# working.net
KiCad netlist of a schematic drawn in EAGLE
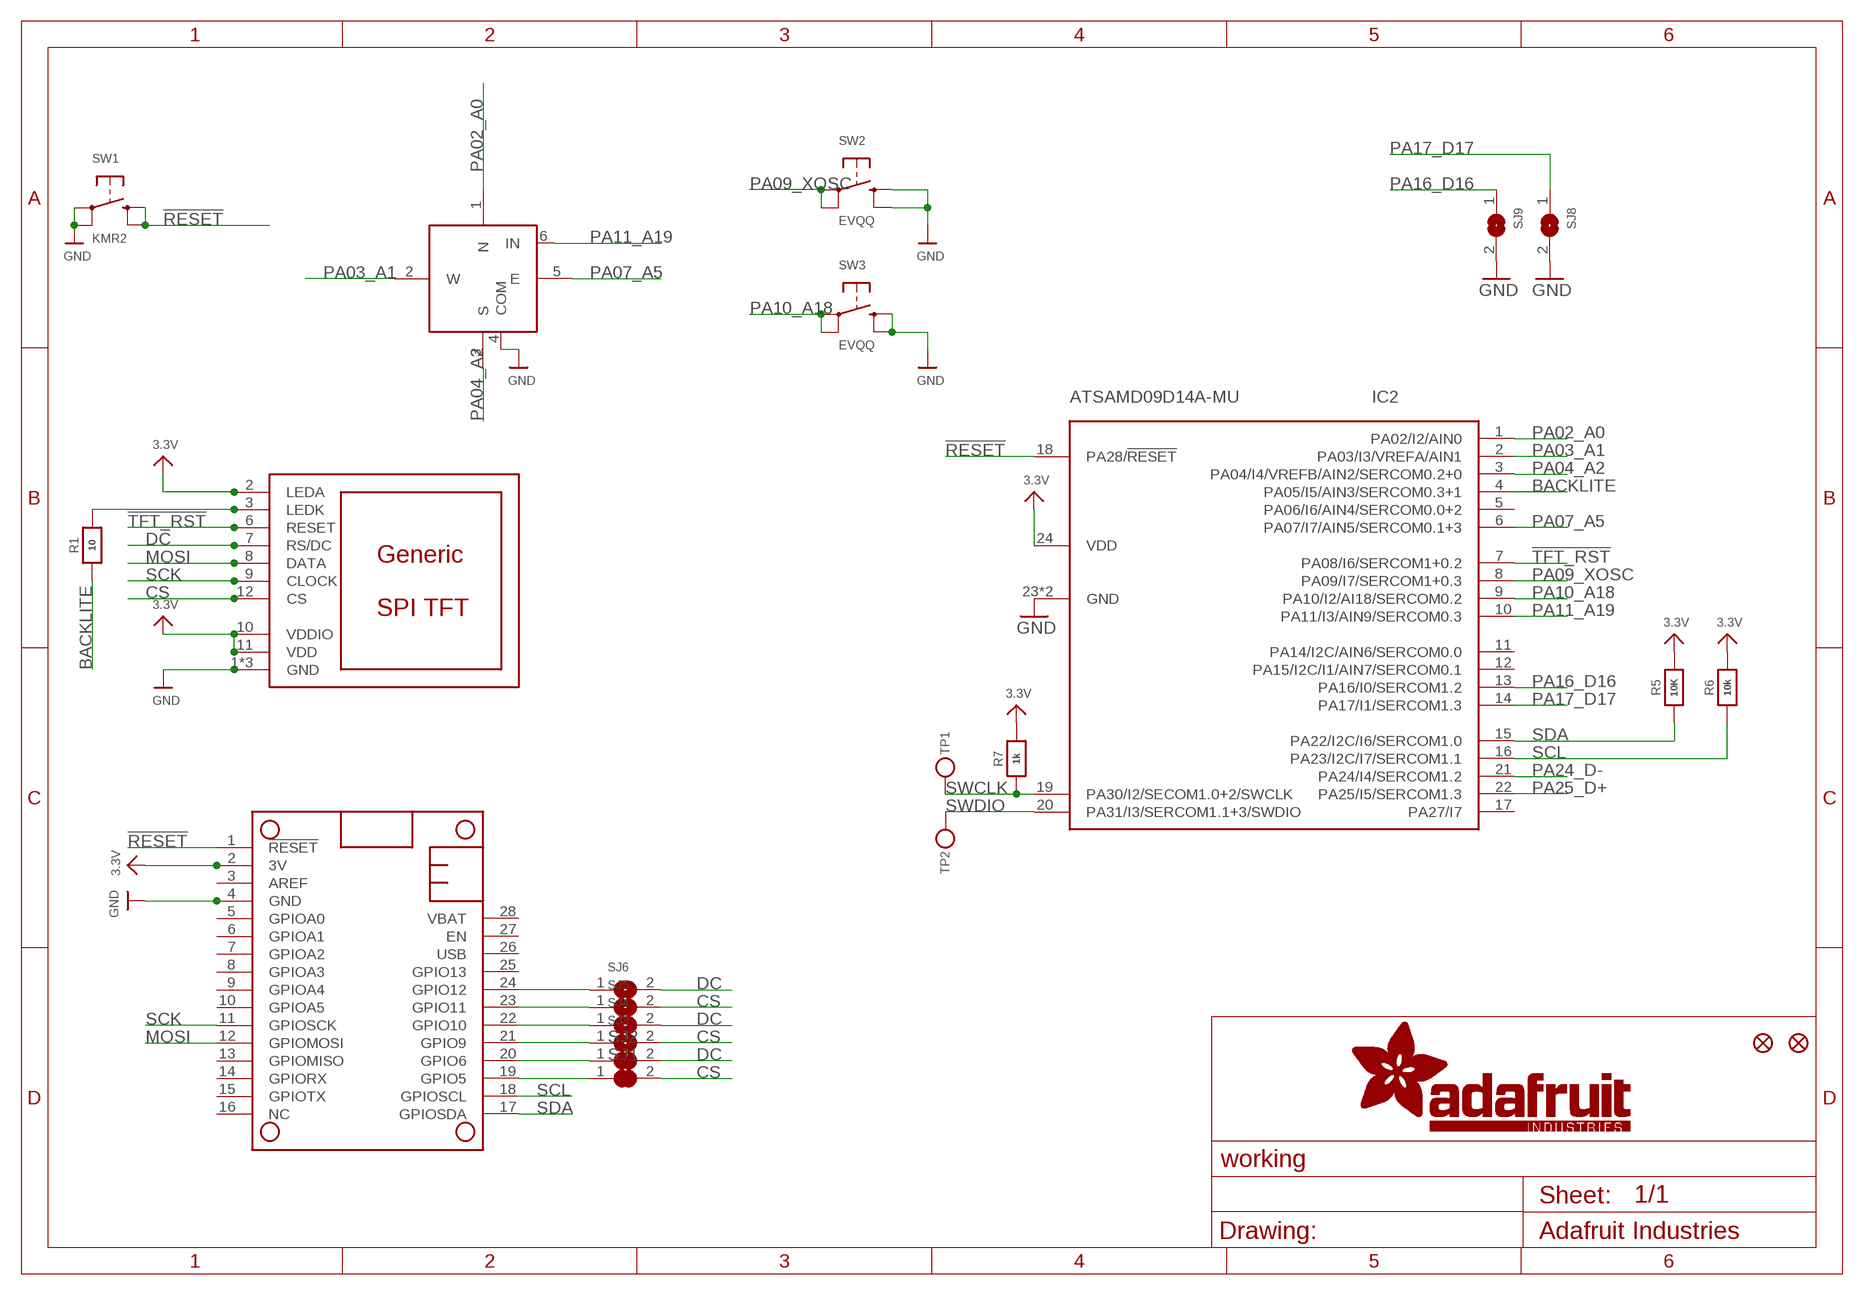
[diagram p0: schematic, sheet 1]

(export (version "E")
  (design (tool "Eeschema 10.0.6"))
  (components
    (comp (ref "FID1")
      (value "FIDUCIAL_1MM")
      (footprint "eagle-import:FIDUCIAL_1MM")
      (libsource (lib "eagle-import") (part "FIDUCIAL_1MM"))
    )
    (comp (ref "FID2")
      (value "FIDUCIAL_1MM")
      (footprint "eagle-import:FIDUCIAL_1MM")
      (libsource (lib "eagle-import") (part "FIDUCIAL_1MM"))
    )
    (comp (ref "IC2")
      (value "ATSAMD09D14A-MU")
      (footprint "eagle-import:QFN24_4MM")
      (libsource (lib "eagle-import") (part "ATSAMD09D14A-MU"))
    )
    (comp (ref "MS1")
      (value "FEATHERWING")
      (footprint "eagle-import:FEATHERWING")
      (libsource (lib "eagle-import") (part "FEATHERWING"))
    )
    (comp (ref "R1")
      (value "10")
      (footprint "eagle-import:0603-NO")
      (libsource (lib "eagle-import") (part "RESISTOR_0603_NOOUT"))
    )
    (comp (ref "R5")
      (value "10K")
      (footprint "eagle-import:0603-NO")
      (libsource (lib "eagle-import") (part "RESISTOR_0603_NOOUT"))
    )
    (comp (ref "R6")
      (value "10k")
      (footprint "eagle-import:0603-NO")
      (libsource (lib "eagle-import") (part "RESISTOR_0603_NOOUT"))
    )
    (comp (ref "R7")
      (value "1k")
      (footprint "eagle-import:0603-NO")
      (libsource (lib "eagle-import") (part "RESISTOR_0603_NOOUT"))
    )
    (comp (ref "SJ1")
      (value "SOLDERJUMPER_CLOSED")
      (footprint "eagle-import:SOLDERJUMPER_CLOSEDWIRE")
      (libsource (lib "eagle-import") (part "SOLDERJUMPER_CLOSED"))
    )
    (comp (ref "SJ2")
      (value "SOLDERJUMPER_CLOSED")
      (footprint "eagle-import:SOLDERJUMPER_CLOSEDWIRE")
      (libsource (lib "eagle-import") (part "SOLDERJUMPER_CLOSED"))
    )
    (comp (ref "SJ3")
      (value "SOLDERJUMPER")
      (footprint "eagle-import:SOLDERJUMPER_ARROW_NOPASTE")
      (libsource (lib "eagle-import") (part "SOLDERJUMPER"))
    )
    (comp (ref "SJ4")
      (value "SOLDERJUMPER")
      (footprint "eagle-import:SOLDERJUMPER_ARROW_NOPASTE")
      (libsource (lib "eagle-import") (part "SOLDERJUMPER"))
    )
    (comp (ref "SJ5")
      (value "SOLDERJUMPER")
      (footprint "eagle-import:SOLDERJUMPER_ARROW_NOPASTE")
      (libsource (lib "eagle-import") (part "SOLDERJUMPER"))
    )
    (comp (ref "SJ6")
      (value "SOLDERJUMPER")
      (footprint "eagle-import:SOLDERJUMPER_ARROW_NOPASTE")
      (libsource (lib "eagle-import") (part "SOLDERJUMPER"))
    )
    (comp (ref "SJ8")
      (value "SOLDERJUMPER")
      (footprint "eagle-import:SOLDERJUMPER_ARROW_NOPASTE")
      (libsource (lib "eagle-import") (part "SOLDERJUMPER"))
    )
    (comp (ref "SJ9")
      (value "SOLDERJUMPER")
      (footprint "eagle-import:SOLDERJUMPER_ARROW_NOPASTE")
      (libsource (lib "eagle-import") (part "SOLDERJUMPER"))
    )
    (comp (ref "SW1")
      (value "KMR2")
      (footprint "eagle-import:BTN_KMR2_4.6X2.8")
      (libsource (lib "eagle-import") (part "SWITCH_TACT_SMT4.6X2.8"))
    )
    (comp (ref "SW2")
      (value "EVQQ")
      (footprint "eagle-import:EVQ-Q2_SMALLER")
      (libsource (lib "eagle-import") (part "SWITCH_TACT_SMT_EVQQ2_SMALL"))
    )
    (comp (ref "SW3")
      (value "EVQQ")
      (footprint "eagle-import:EVQ-Q2_SMALLER")
      (libsource (lib "eagle-import") (part "SWITCH_TACT_SMT_EVQQ2_SMALL"))
    )
    (comp (ref "SW4")
      (value "NAVSWITCHSKQUABAUE010")
      (footprint "eagle-import:SKQUBAE010")
      (libsource (lib "eagle-import") (part "NAVSWITCHSKQUABAUE010"))
    )
    (comp (ref "TP1")
      (value "TESTPOINTROUND2MM")
      (footprint "eagle-import:TESTPOINT_ROUND_2MM")
      (libsource (lib "eagle-import") (part "TESTPOINTROUND2MM"))
    )
    (comp (ref "TP2")
      (value "TESTPOINTROUND2MM")
      (footprint "eagle-import:TESTPOINT_ROUND_2MM")
      (libsource (lib "eagle-import") (part "TESTPOINTROUND2MM"))
    )
    (comp (ref "U$2")
      (value "DISP_LCD_0.9IN_160X80")
      (footprint "eagle-import:TFT_0.96IN_160X80")
      (libsource (lib "eagle-import") (part "DISP_LCD_0.9IN_160X80"))
    )
  )
  (nets
    (net (code "1") (name "/BACKLITE") (class "Default")
      (node (ref "IC2") (pin "4") (pinfunction "PA05/I5/AIN3/SERCOM0.3+1_4") (pintype "bidirectional"))
      (node (ref "R1") (pin "1") (pinfunction "1_1") (pintype "passive"))
    )
    (net (code "2") (name "/CS") (class "Default")
      (node (ref "SJ1") (pin "2") (pinfunction "2_2") (pintype "passive"))
      (node (ref "SJ3") (pin "2") (pinfunction "2_2") (pintype "passive"))
      (node (ref "SJ5") (pin "2") (pinfunction "2_2") (pintype "passive"))
      (node (ref "U$2") (pin "12") (pinfunction "CS_12") (pintype "input"))
    )
    (net (code "3") (name "/DC") (class "Default")
      (node (ref "SJ2") (pin "2") (pinfunction "2_2") (pintype "passive"))
      (node (ref "SJ4") (pin "2") (pinfunction "2_2") (pintype "passive"))
      (node (ref "SJ6") (pin "2") (pinfunction "2_2") (pintype "passive"))
      (node (ref "U$2") (pin "7") (pinfunction "RS/DC_7") (pintype "input"))
    )
    (net (code "4") (name "/MOSI") (class "Default")
      (node (ref "MS1") (pin "12") (pinfunction "GPIOMOSI_12") (pintype "bidirectional"))
      (node (ref "U$2") (pin "8") (pinfunction "DATA_8") (pintype "bidirectional"))
    )
    (net (code "5") (name "/PA02_A0") (class "Default")
      (node (ref "IC2") (pin "1") (pinfunction "PA02/I2/AIN0_1") (pintype "bidirectional"))
      (node (ref "SW4") (pin "1") (pinfunction "N_1") (pintype "bidirectional"))
    )
    (net (code "6") (name "/PA03_A1") (class "Default")
      (node (ref "IC2") (pin "2") (pinfunction "PA03/I3/VREFA/AIN1_2") (pintype "bidirectional"))
      (node (ref "SW4") (pin "2") (pinfunction "W_2") (pintype "bidirectional"))
    )
    (net (code "7") (name "/PA04_A2") (class "Default")
      (node (ref "IC2") (pin "3") (pinfunction "PA04/I4/VREFB/AIN2/SERCOM0.2+0_3") (pintype "bidirectional"))
      (node (ref "SW4") (pin "3") (pinfunction "S_3") (pintype "bidirectional"))
    )
    (net (code "8") (name "/PA07_A5") (class "Default")
      (node (ref "IC2") (pin "6") (pinfunction "PA07/I7/AIN5/SERCOM0.1+3_6") (pintype "bidirectional"))
      (node (ref "SW4") (pin "5") (pinfunction "E_5") (pintype "bidirectional"))
    )
    (net (code "9") (name "/PA09_XOSC") (class "Default")
      (node (ref "IC2") (pin "8") (pinfunction "PA09/I7/SERCOM1+0.3_8") (pintype "bidirectional"))
      (node (ref "SW2") (pin "A") (pinfunction "P_A") (pintype "passive"))
      (node (ref "SW2") (pin "A'") (pinfunction "P1_A'") (pintype "passive"))
    )
    (net (code "10") (name "/PA10_A18") (class "Default")
      (node (ref "IC2") (pin "9") (pinfunction "PA10/I2/AI18/SERCOM0.2_9") (pintype "bidirectional"))
      (node (ref "SW3") (pin "A") (pinfunction "P_A") (pintype "passive"))
      (node (ref "SW3") (pin "A'") (pinfunction "P1_A'") (pintype "passive"))
    )
    (net (code "11") (name "/PA11_A19") (class "Default")
      (node (ref "IC2") (pin "10") (pinfunction "PA11/I3/AIN9/SERCOM0.3_10") (pintype "bidirectional"))
      (node (ref "SW4") (pin "6") (pinfunction "IN_6") (pintype "bidirectional"))
    )
    (net (code "12") (name "/PA16_D16") (class "Default")
      (node (ref "IC2") (pin "13") (pinfunction "PA16/I0/SERCOM1.2_13") (pintype "bidirectional"))
      (node (ref "SJ9") (pin "1") (pinfunction "1_1") (pintype "passive"))
    )
    (net (code "13") (name "/PA17_D17") (class "Default")
      (node (ref "IC2") (pin "14") (pinfunction "PA17/I1/SERCOM1.3_14") (pintype "bidirectional"))
      (node (ref "SJ8") (pin "1") (pinfunction "1_1") (pintype "passive"))
    )
    (net (code "14") (name "/PA24_D-") (class "Default")
      (node (ref "IC2") (pin "21") (pinfunction "PA24/I4/SERCOM1.2_21") (pintype "bidirectional"))
    )
    (net (code "15") (name "/PA25_D+") (class "Default")
      (node (ref "IC2") (pin "22") (pinfunction "PA25/I5/SERCOM1.3_22") (pintype "bidirectional"))
    )
    (net (code "16") (name "/SCK") (class "Default")
      (node (ref "MS1") (pin "11") (pinfunction "GPIOSCK_11") (pintype "bidirectional"))
      (node (ref "U$2") (pin "9") (pinfunction "CLOCK_9") (pintype "input"))
    )
    (net (code "17") (name "/SCL") (class "Default")
      (node (ref "IC2") (pin "16") (pinfunction "PA23/I2C/I7/SERCOM1.1_16") (pintype "bidirectional"))
      (node (ref "MS1") (pin "18") (pinfunction "GPIOSCL_18") (pintype "bidirectional"))
      (node (ref "R6") (pin "1") (pinfunction "1_1") (pintype "passive"))
    )
    (net (code "18") (name "/SDA") (class "Default")
      (node (ref "IC2") (pin "15") (pinfunction "PA22/I2C/I6/SERCOM1.0_15") (pintype "bidirectional"))
      (node (ref "MS1") (pin "17") (pinfunction "GPIOSDA_17") (pintype "bidirectional"))
      (node (ref "R5") (pin "1") (pinfunction "1_1") (pintype "passive"))
    )
    (net (code "19") (name "/SWCLK") (class "Default")
      (node (ref "IC2") (pin "19") (pinfunction "PA30/I2/SECOM1.0+2/SWCLK_19") (pintype "bidirectional"))
      (node (ref "R7") (pin "1") (pinfunction "1_1") (pintype "passive"))
      (node (ref "TP1") (pin "P$1") (pinfunction "P$1_P$1") (pintype "bidirectional"))
    )
    (net (code "20") (name "/SWDIO") (class "Default")
      (node (ref "IC2") (pin "20") (pinfunction "PA31/I3/SERCOM1.1+3/SWDIO_20") (pintype "bidirectional"))
      (node (ref "TP2") (pin "P$1") (pinfunction "P$1_P$1") (pintype "bidirectional"))
    )
    (net (code "21") (name "/USB") (class "Default")
      (node (ref "MS1") (pin "26") (pinfunction "USB_26") (pintype "power_in"))
    )
    (net (code "22") (name "/VBAT") (class "Default")
      (node (ref "MS1") (pin "28") (pinfunction "VBAT_28") (pintype "power_in"))
    )
    (net (code "23") (name "/~{RESET}") (class "Default")
      (node (ref "IC2") (pin "18") (pinfunction "PA28/~{RESET}_18") (pintype "bidirectional"))
      (node (ref "MS1") (pin "1") (pinfunction "~{RESET}_1") (pintype "input"))
      (node (ref "SW1") (pin "B") (pinfunction "S_B") (pintype "passive"))
      (node (ref "SW1") (pin "B'") (pinfunction "S1_B'") (pintype "passive"))
    )
    (net (code "24") (name "/~{TFT_RST}") (class "Default")
      (node (ref "IC2") (pin "7") (pinfunction "PA08/I6/SERCOM1+0.2_7") (pintype "bidirectional"))
      (node (ref "U$2") (pin "6") (pinfunction "RESET_6") (pintype "input"))
    )
    (net (code "25") (name "3.3V") (class "Default")
      (node (ref "IC2") (pin "24") (pinfunction "VDD_24") (pintype "power_in"))
      (node (ref "MS1") (pin "2") (pinfunction "3V_2") (pintype "power_in"))
      (node (ref "R5") (pin "2") (pinfunction "2_2") (pintype "passive"))
      (node (ref "R6") (pin "2") (pinfunction "2_2") (pintype "passive"))
      (node (ref "R7") (pin "2") (pinfunction "2_2") (pintype "passive"))
      (node (ref "U$2") (pin "10") (pinfunction "VDDIO_10") (pintype "power_in"))
      (node (ref "U$2") (pin "11") (pinfunction "VDD_11") (pintype "power_in"))
      (node (ref "U$2") (pin "2") (pinfunction "LEDA_2") (pintype "input"))
    )
    (net (code "26") (name "GND") (class "Default")
      (node (ref "IC2") (pin "23") (pinfunction "GND_23") (pintype "power_in"))
      (node (ref "IC2") (pin "THERM") (pinfunction "GND_THERM") (pintype "power_in"))
      (node (ref "MS1") (pin "4") (pinfunction "GND_4") (pintype "power_in"))
      (node (ref "SJ8") (pin "2") (pinfunction "2_2") (pintype "passive"))
      (node (ref "SJ9") (pin "2") (pinfunction "2_2") (pintype "passive"))
      (node (ref "SW1") (pin "A") (pinfunction "P_A") (pintype "passive"))
      (node (ref "SW1") (pin "A'") (pinfunction "P1_A'") (pintype "passive"))
      (node (ref "SW2") (pin "B") (pinfunction "S_B") (pintype "passive"))
      (node (ref "SW2") (pin "B'") (pinfunction "S1_B'") (pintype "passive"))
      (node (ref "SW3") (pin "B") (pinfunction "S_B") (pintype "passive"))
      (node (ref "SW3") (pin "B'") (pinfunction "S1_B'") (pintype "passive"))
      (node (ref "SW4") (pin "4") (pinfunction "COM_4") (pintype "bidirectional"))
      (node (ref "U$2") (pin "1") (pinfunction "GND_1") (pintype "power_in"))
      (node (ref "U$2") (pin "13") (pinfunction "GND_13") (pintype "power_in"))
      (node (ref "U$2") (pin "5") (pinfunction "GND_5") (pintype "power_in"))
    )
    (net (code "27") (name "Net-(MS1-GPIO5)") (class "Default")
      (node (ref "MS1") (pin "19") (pinfunction "GPIO5_19") (pintype "bidirectional"))
      (node (ref "SJ1") (pin "1") (pinfunction "1_1") (pintype "passive"))
    )
    (net (code "28") (name "Net-(MS1-GPIO6)") (class "Default")
      (node (ref "MS1") (pin "20") (pinfunction "GPIO6_20") (pintype "bidirectional"))
      (node (ref "SJ2") (pin "1") (pinfunction "1_1") (pintype "passive"))
    )
    (net (code "29") (name "Net-(MS1-GPIO9)") (class "Default")
      (node (ref "MS1") (pin "21") (pinfunction "GPIO9_21") (pintype "bidirectional"))
      (node (ref "SJ3") (pin "1") (pinfunction "1_1") (pintype "passive"))
    )
    (net (code "30") (name "Net-(MS1-GPIO10)") (class "Default")
      (node (ref "MS1") (pin "22") (pinfunction "GPIO10_22") (pintype "bidirectional"))
      (node (ref "SJ4") (pin "1") (pinfunction "1_1") (pintype "passive"))
    )
    (net (code "31") (name "Net-(MS1-GPIO11)") (class "Default")
      (node (ref "MS1") (pin "23") (pinfunction "GPIO11_23") (pintype "bidirectional"))
      (node (ref "SJ5") (pin "1") (pinfunction "1_1") (pintype "passive"))
    )
    (net (code "32") (name "Net-(MS1-GPIO12)") (class "Default")
      (node (ref "MS1") (pin "24") (pinfunction "GPIO12_24") (pintype "bidirectional"))
      (node (ref "SJ6") (pin "1") (pinfunction "1_1") (pintype "passive"))
    )
    (net (code "33") (name "Net-(U$2-LEDK)") (class "Default")
      (node (ref "R1") (pin "2") (pinfunction "2_2") (pintype "passive"))
      (node (ref "U$2") (pin "3") (pinfunction "LEDK_3") (pintype "input"))
    )
    (net (code "34") (name "unconnected-(IC2-PA06{slash}I6{slash}AIN4{slash}SERCOM0.0+2-Pad5)") (class "Default")
      (node (ref "IC2") (pin "5") (pinfunction "PA06/I6/AIN4/SERCOM0.0+2_5") (pintype "bidirectional"))
    )
    (net (code "35") (name "unconnected-(IC2-PA14{slash}I2C{slash}AIN6{slash}SERCOM0.0-Pad11)") (class "Default")
      (node (ref "IC2") (pin "11") (pinfunction "PA14/I2C/AIN6/SERCOM0.0_11") (pintype "bidirectional"))
    )
    (net (code "36") (name "unconnected-(IC2-PA15{slash}I2C{slash}I1{slash}AIN7{slash}SERCOM0.1-Pad12)") (class "Default")
      (node (ref "IC2") (pin "12") (pinfunction "PA15/I2C/I1/AIN7/SERCOM0.1_12") (pintype "bidirectional"))
    )
    (net (code "37") (name "unconnected-(IC2-PA27{slash}I7-Pad17)") (class "Default")
      (node (ref "IC2") (pin "17") (pinfunction "PA27/I7_17") (pintype "bidirectional"))
    )
    (net (code "38") (name "unconnected-(MS1-AREF-Pad3)") (class "Default")
      (node (ref "MS1") (pin "3") (pinfunction "AREF_3") (pintype "passive"))
    )
    (net (code "39") (name "unconnected-(MS1-EN-Pad27)") (class "Default")
      (node (ref "MS1") (pin "27") (pinfunction "EN_27") (pintype "passive"))
    )
    (net (code "40") (name "unconnected-(MS1-GPIO13-Pad25)") (class "Default")
      (node (ref "MS1") (pin "25") (pinfunction "GPIO13_25") (pintype "bidirectional"))
    )
    (net (code "41") (name "unconnected-(MS1-GPIOA0-Pad5)") (class "Default")
      (node (ref "MS1") (pin "5") (pinfunction "GPIOA0_5") (pintype "bidirectional"))
    )
    (net (code "42") (name "unconnected-(MS1-GPIOA1-Pad6)") (class "Default")
      (node (ref "MS1") (pin "6") (pinfunction "GPIOA1_6") (pintype "bidirectional"))
    )
    (net (code "43") (name "unconnected-(MS1-GPIOA2-Pad7)") (class "Default")
      (node (ref "MS1") (pin "7") (pinfunction "GPIOA2_7") (pintype "bidirectional"))
    )
    (net (code "44") (name "unconnected-(MS1-GPIOA3-Pad8)") (class "Default")
      (node (ref "MS1") (pin "8") (pinfunction "GPIOA3_8") (pintype "bidirectional"))
    )
    (net (code "45") (name "unconnected-(MS1-GPIOA4-Pad9)") (class "Default")
      (node (ref "MS1") (pin "9") (pinfunction "GPIOA4_9") (pintype "bidirectional"))
    )
    (net (code "46") (name "unconnected-(MS1-GPIOA5-Pad10)") (class "Default")
      (node (ref "MS1") (pin "10") (pinfunction "GPIOA5_10") (pintype "bidirectional"))
    )
    (net (code "47") (name "unconnected-(MS1-GPIOMISO-Pad13)") (class "Default")
      (node (ref "MS1") (pin "13") (pinfunction "GPIOMISO_13") (pintype "bidirectional"))
    )
    (net (code "48") (name "unconnected-(MS1-GPIORX-Pad14)") (class "Default")
      (node (ref "MS1") (pin "14") (pinfunction "GPIORX_14") (pintype "bidirectional"))
    )
    (net (code "49") (name "unconnected-(MS1-GPIOTX-Pad15)") (class "Default")
      (node (ref "MS1") (pin "15") (pinfunction "GPIOTX_15") (pintype "bidirectional"))
    )
    (net (code "50") (name "unconnected-(MS1-NC-Pad16)") (class "Default")
      (node (ref "MS1") (pin "16") (pinfunction "NC_16") (pintype "passive"))
    )
  )
)
